# feederboard.net
KiCad netlist of a schematic drawn in EAGLE
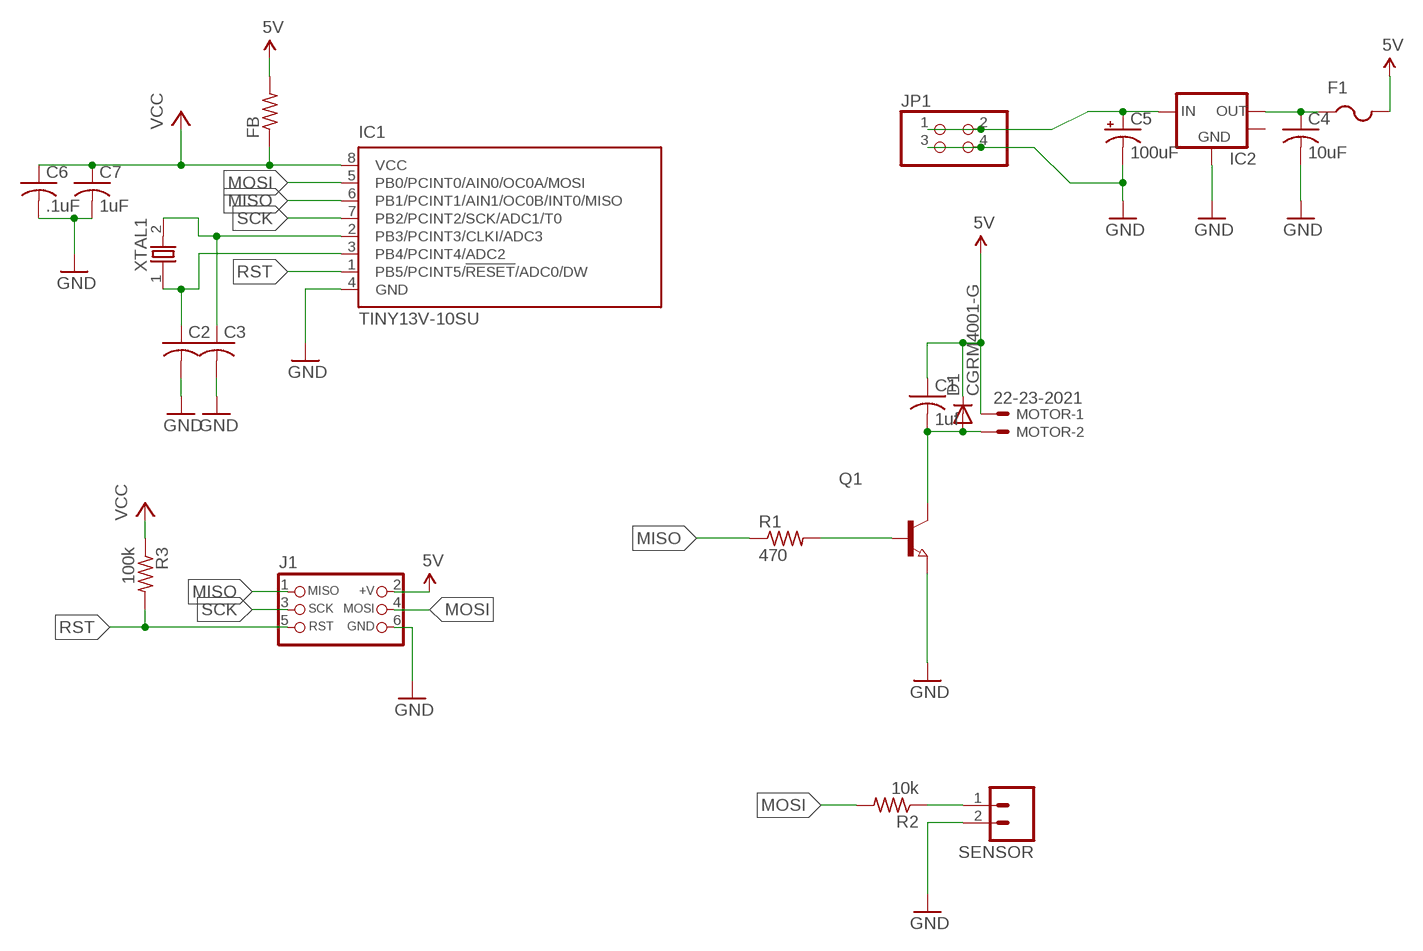
[diagram p0: schematic, sheet 1]

(export (version "E")
  (design (tool "Eeschema 10.0.6"))
  (components
    (comp (ref "C1")
      (value "1uf")
      (footprint "eagle-import:C0805K")
      (libsource (lib "eagle-import") (part "C-USC0805K"))
    )
    (comp (ref "C2")
      (value "C-USC0805")
      (footprint "eagle-import:C0805")
      (libsource (lib "eagle-import") (part "C-USC0805"))
    )
    (comp (ref "C3")
      (value "C-USC0805")
      (footprint "eagle-import:C0805")
      (libsource (lib "eagle-import") (part "C-USC0805"))
    )
    (comp (ref "C4")
      (value "10uF")
      (footprint "eagle-import:C0805K")
      (libsource (lib "eagle-import") (part "C-USC0805K"))
    )
    (comp (ref "C5")
      (value "100uF")
      (footprint "eagle-import:PANASONIC_C")
      (libsource (lib "eagle-import") (part "CPOL-USC"))
    )
    (comp (ref "C6")
      (value ".1uF")
      (footprint "eagle-import:C0603")
      (libsource (lib "eagle-import") (part "C-USC0603"))
    )
    (comp (ref "C7")
      (value "1uF")
      (footprint "eagle-import:C0603")
      (libsource (lib "eagle-import") (part "C-USC0603"))
    )
    (comp (ref "D1")
      (value "CGRM4001-G")
      (footprint "eagle-import:SOD-123_MINI-SMA")
      (libsource (lib "eagle-import") (part "CGRM400-G1"))
    )
    (comp (ref "F1")
      (value "PTCFUSE-1206")
      (footprint "eagle-import:R1206")
      (libsource (lib "eagle-import") (part "PTCFUSE-1206"))
    )
    (comp (ref "FB")
      (value "R-US_R0805")
      (footprint "eagle-import:R0805")
      (libsource (lib "eagle-import") (part "R-US_R0805"))
    )
    (comp (ref "IC1")
      (value "TINY13V-10SU")
      (footprint "eagle-import:8S2")
      (fields (field (name "MPN") "ATTINY13V-10SU"))
      (libsource (lib "eagle-import") (part "TINY13SUV-10"))
    )
    (comp (ref "IC2")
      (value "V_REG_LM1117SOT223")
      (footprint "eagle-import:SOT223")
      (libsource (lib "eagle-import") (part "V_REG_LM1117SOT223"))
    )
    (comp (ref "J1")
      (value "CON_HEADER_PRG_AVR_ICSP_ETCH")
      (footprint "eagle-import:HEADER_PRG_2X03_ETCH")
      (libsource (lib "eagle-import") (part "CON_HEADER_PRG_AVR_ICSP_ETCH"))
    )
    (comp (ref "JP1")
      (value "PINHD-2X2/90")
      (footprint "eagle-import:2X02_90")
      (libsource (lib "eagle-import") (part "PINHD-2X2/90"))
    )
    (comp (ref "MOTOR")
      (value "22-23-2021")
      (footprint "eagle-import:22-23-2021")
      (fields (field (name "MF") "MOLEX"))
      (libsource (lib "eagle-import") (part "22-23-2021"))
    )
    (comp (ref "Q1")
      (value "NPN-TRANSISTOR_SOT23")
      (footprint "eagle-import:SOT23")
      (libsource (lib "eagle-import") (part "NPN-TRANSISTOR_SOT23"))
    )
    (comp (ref "R1")
      (value "470")
      (footprint "eagle-import:R0805")
      (libsource (lib "eagle-import") (part "R-US_R0805"))
    )
    (comp (ref "R2")
      (value "10k")
      (footprint "eagle-import:R0805")
      (libsource (lib "eagle-import") (part "R-US_R0805"))
    )
    (comp (ref "R3")
      (value "100k")
      (footprint "eagle-import:R0805")
      (libsource (lib "eagle-import") (part "R-US_R0805"))
    )
    (comp (ref "SENSOR")
      (value "M02JST-PTH-2")
      (footprint "eagle-import:JST-2-PTH")
      (libsource (lib "eagle-import") (part "M02JST-PTH-2"))
    )
    (comp (ref "XTAL1")
      (value "OSC-XTAL")
      (footprint "eagle-import:HC-49U-OR-DIP")
      (libsource (lib "eagle-import") (part "OSC-XTAL"))
    )
  )
  (nets
    (net (code "1") (name "/OUT") (class "Default")
      (node (ref "IC2") (pin "4") (pinfunction "OUT_4") (pintype "power_in"))
    )
    (net (code "2") (name "5V") (class "Default")
      (node (ref "C1") (pin "1") (pinfunction "1_1") (pintype "passive"))
      (node (ref "D1") (pin "C") (pinfunction "C_C") (pintype "passive"))
      (node (ref "F1") (pin "2") (pinfunction "2_2") (pintype "passive"))
      (node (ref "FB") (pin "2") (pinfunction "2_2") (pintype "passive"))
      (node (ref "J1") (pin "2") (pinfunction "+V_2") (pintype "passive"))
      (node (ref "MOTOR") (pin "1") (pinfunction "S_1") (pintype "passive"))
    )
    (net (code "3") (name "GND") (class "Default")
      (node (ref "C2") (pin "2") (pinfunction "2_2") (pintype "passive"))
      (node (ref "C3") (pin "2") (pinfunction "2_2") (pintype "passive"))
      (node (ref "C4") (pin "2") (pinfunction "2_2") (pintype "passive"))
      (node (ref "C5") (pin "-") (pinfunction "-_-") (pintype "passive"))
      (node (ref "C6") (pin "2") (pinfunction "2_2") (pintype "passive"))
      (node (ref "C7") (pin "2") (pinfunction "2_2") (pintype "passive"))
      (node (ref "IC1") (pin "4") (pinfunction "GND_4") (pintype "power_in"))
      (node (ref "IC2") (pin "1") (pinfunction "GND_1") (pintype "input"))
      (node (ref "J1") (pin "6") (pinfunction "GND_6") (pintype "passive"))
      (node (ref "JP1") (pin "3") (pinfunction "3_3") (pintype "passive"))
      (node (ref "JP1") (pin "4") (pinfunction "4_4") (pintype "passive"))
      (node (ref "Q1") (pin "2") (pinfunction "E_2") (pintype "passive"))
      (node (ref "SENSOR") (pin "2") (pinfunction "2_2") (pintype "passive"))
    )
    (net (code "4") (name "MISO") (class "Default")
      (node (ref "IC1") (pin "6") (pinfunction "PB1/PCINT1/AIN1/OC0B/INT0/MISO_6") (pintype "bidirectional"))
      (node (ref "J1") (pin "1") (pinfunction "MISO_1") (pintype "passive"))
      (node (ref "R1") (pin "1") (pinfunction "1_1") (pintype "passive"))
    )
    (net (code "5") (name "MOSI") (class "Default")
      (node (ref "IC1") (pin "5") (pinfunction "PB0/PCINT0/AIN0/OC0A/MOSI_5") (pintype "bidirectional"))
      (node (ref "J1") (pin "4") (pinfunction "MOSI_4") (pintype "passive"))
      (node (ref "R2") (pin "2") (pinfunction "2_2") (pintype "passive"))
    )
    (net (code "6") (name "Net-(IC1-PB3{slash}PCINT3{slash}CLKI{slash}ADC3)") (class "Default")
      (node (ref "C3") (pin "1") (pinfunction "1_1") (pintype "passive"))
      (node (ref "IC1") (pin "2") (pinfunction "PB3/PCINT3/CLKI/ADC3_2") (pintype "bidirectional"))
      (node (ref "XTAL1") (pin "2") (pinfunction "2_2") (pintype "passive"))
    )
    (net (code "7") (name "Net-(IC1-PB4{slash}PCINT4{slash}ADC2)") (class "Default")
      (node (ref "C2") (pin "1") (pinfunction "1_1") (pintype "passive"))
      (node (ref "IC1") (pin "3") (pinfunction "PB4/PCINT4/ADC2_3") (pintype "bidirectional"))
      (node (ref "XTAL1") (pin "1") (pinfunction "1_1") (pintype "passive"))
    )
    (net (code "8") (name "Net-(IC2-IN)") (class "Default")
      (node (ref "C5") (pin "+") (pinfunction "+_+") (pintype "passive"))
      (node (ref "IC2") (pin "3") (pinfunction "IN_3") (pintype "input"))
      (node (ref "JP1") (pin "1") (pinfunction "1_1") (pintype "passive"))
      (node (ref "JP1") (pin "2") (pinfunction "2_2") (pintype "passive"))
    )
    (net (code "9") (name "Net-(IC2-VR-OUTSM)") (class "Default")
      (node (ref "C4") (pin "1") (pinfunction "1_1") (pintype "passive"))
      (node (ref "F1") (pin "1") (pinfunction "1_1") (pintype "passive"))
      (node (ref "IC2") (pin "2") (pinfunction "VR-OUTSM_2") (pintype "power_in"))
    )
    (net (code "10") (name "Net-(MOTORB-S)") (class "Default")
      (node (ref "C1") (pin "2") (pinfunction "2_2") (pintype "passive"))
      (node (ref "D1") (pin "A") (pinfunction "A_A") (pintype "passive"))
      (node (ref "MOTOR") (pin "2") (pinfunction "S_2") (pintype "passive"))
      (node (ref "Q1") (pin "3") (pinfunction "C_3") (pintype "passive"))
    )
    (net (code "11") (name "Net-(Q1-B)") (class "Default")
      (node (ref "Q1") (pin "1") (pinfunction "B_1") (pintype "passive"))
      (node (ref "R1") (pin "2") (pinfunction "2_2") (pintype "passive"))
    )
    (net (code "12") (name "Net-(R2-Pad1)") (class "Default")
      (node (ref "R2") (pin "1") (pinfunction "1_1") (pintype "passive"))
      (node (ref "SENSOR") (pin "1") (pinfunction "1_1") (pintype "passive"))
    )
    (net (code "13") (name "RST") (class "Default")
      (node (ref "IC1") (pin "1") (pinfunction "PB5/PCINT5/~{RESET}/ADC0/DW_1") (pintype "bidirectional"))
      (node (ref "J1") (pin "5") (pinfunction "RST_5") (pintype "passive"))
      (node (ref "R3") (pin "2") (pinfunction "2_2") (pintype "passive"))
    )
    (net (code "14") (name "SCK") (class "Default")
      (node (ref "IC1") (pin "7") (pinfunction "PB2/PCINT2/SCK/ADC1/T0_7") (pintype "bidirectional"))
      (node (ref "J1") (pin "3") (pinfunction "SCK_3") (pintype "passive"))
    )
    (net (code "15") (name "VCC") (class "Default")
      (node (ref "C6") (pin "1") (pinfunction "1_1") (pintype "passive"))
      (node (ref "C7") (pin "1") (pinfunction "1_1") (pintype "passive"))
      (node (ref "FB") (pin "1") (pinfunction "1_1") (pintype "passive"))
      (node (ref "IC1") (pin "8") (pinfunction "VCC_8") (pintype "power_in"))
      (node (ref "R3") (pin "1") (pinfunction "1_1") (pintype "passive"))
    )
  )
)
